# design.net
KiCad netlist of a schematic drawn in Altium Designer
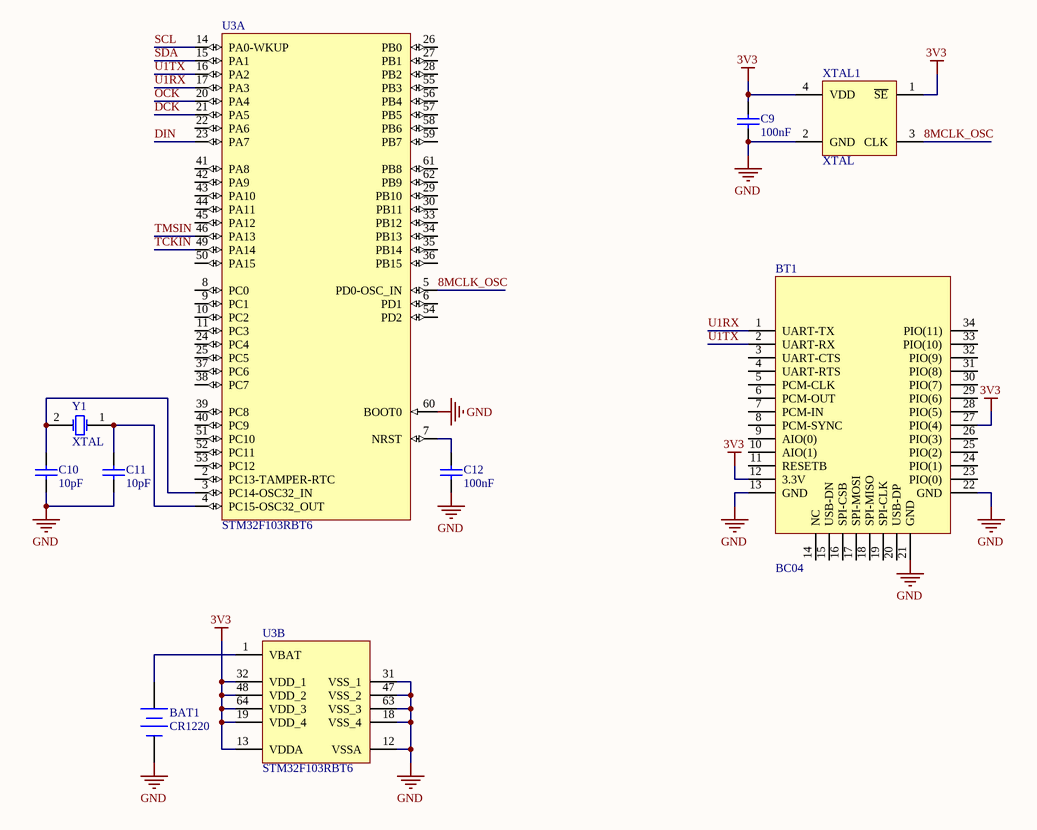
[diagram p0: 单片机.SchDoc]

(export (version "E")
  (design (tool "Eeschema 10.0.6"))
  (components
    (comp (ref "BAT1")
      (value "CR1220")
      (footprint "BAT-CR1220")
      (description "Multicell Battery")
      (fields (field (name "PUBLISHER") "Altium Limited"))
      (libsource (lib "yitiandelan") (part "Battery"))
    )
    (comp (ref "BT1") (value "BC04") (footprint "BC04") (libsource (lib "yitiandelan") (part "BC04")))
    (comp (ref "C9")
      (value "100nF")
      (footprint "0805")
      (description "Capacitor")
      (fields (field (name "PUBLISHER") "Altium Limited"))
      (libsource (lib "yitiandelan") (part "Cap"))
    )
    (comp (ref "C10")
      (value "10pF")
      (footprint "0805")
      (description "Capacitor")
      (fields (field (name "PUBLISHER") "Altium Limited"))
      (libsource (lib "yitiandelan") (part "Cap"))
    )
    (comp (ref "C11")
      (value "10pF")
      (footprint "0805")
      (description "Capacitor")
      (fields (field (name "PUBLISHER") "Altium Limited"))
      (libsource (lib "yitiandelan") (part "Cap"))
    )
    (comp (ref "C12")
      (value "100nF")
      (footprint "0805")
      (description "Capacitor")
      (fields (field (name "PUBLISHER") "Altium Limited"))
      (libsource (lib "yitiandelan") (part "Cap"))
    )
    (comp (ref "U3")
      (value "STM32F103RBT6")
      (footprint "LQFP-64")
      (libsource (lib "yitiandelan") (part "STM32F103RBT6"))
    )
    (comp (ref "XTAL1")
      (value "XTAL")
      (footprint "XTAL7050")
      (libsource (lib "yitiandelan") (part "XTAL_SMD"))
    )
    (comp (ref "Y1")
      (value "XTAL")
      (footprint "XTAL-32768")
      (description "Crystal Oscillator")
      (fields (field (name "PUBLISHER") "Altium Limited"))
      (libsource (lib "yitiandelan") (part "XTAL"))
    )
  )
  (nets
    (net (code "1") (name "/8MCLK_OSC") (class "Default")
      (node (ref "U3") (pin "5") (pinfunction "PD0-OSC_IN_5") (pintype "bidirectional"))
      (node (ref "XTAL1") (pin "3") (pinfunction "CLK_3") (pintype "passive"))
    )
    (net (code "2") (name "/DCK") (class "Default")
      (node (ref "U3") (pin "21") (pinfunction "PA5_21") (pintype "bidirectional"))
    )
    (net (code "3") (name "/DIN") (class "Default")
      (node (ref "U3") (pin "23") (pinfunction "PA7_23") (pintype "bidirectional"))
    )
    (net (code "4") (name "/OCK") (class "Default")
      (node (ref "U3") (pin "20") (pinfunction "PA4_20") (pintype "bidirectional"))
    )
    (net (code "5") (name "/SCL") (class "Default")
      (node (ref "U3") (pin "14") (pinfunction "PA0-WKUP_14") (pintype "bidirectional"))
    )
    (net (code "6") (name "/SDA") (class "Default")
      (node (ref "U3") (pin "15") (pinfunction "PA1_15") (pintype "bidirectional"))
    )
    (net (code "7") (name "/TCKIN") (class "Default")
      (node (ref "U3") (pin "49") (pinfunction "PA14_49") (pintype "bidirectional"))
    )
    (net (code "8") (name "/TMSIN") (class "Default")
      (node (ref "U3") (pin "46") (pinfunction "PA13_46") (pintype "bidirectional"))
    )
    (net (code "9") (name "/U1RX") (class "Default")
      (node (ref "BT1") (pin "1") (pinfunction "UART-TX_1") (pintype "passive"))
      (node (ref "U3") (pin "17") (pinfunction "PA3_17") (pintype "bidirectional"))
    )
    (net (code "10") (name "/U1TX") (class "Default")
      (node (ref "BT1") (pin "2") (pinfunction "UART-RX_2") (pintype "passive"))
      (node (ref "U3") (pin "16") (pinfunction "PA2_16") (pintype "bidirectional"))
    )
    (net (code "11") (name "3V3") (class "Default")
      (node (ref "BT1") (pin "12") (pinfunction "3.3V_12") (pintype "passive"))
      (node (ref "BT1") (pin "27") (pinfunction "PIO(4)_27") (pintype "passive"))
      (node (ref "C9") (pin "2") (pinfunction "2_2") (pintype "passive"))
      (node (ref "U3") (pin "13") (pinfunction "VDDA_13") (pintype "power_in"))
      (node (ref "U3") (pin "19") (pinfunction "VDD_4_19") (pintype "power_in"))
      (node (ref "U3") (pin "32") (pinfunction "VDD_1_32") (pintype "power_in"))
      (node (ref "U3") (pin "48") (pinfunction "VDD_2_48") (pintype "power_in"))
      (node (ref "U3") (pin "64") (pinfunction "VDD_3_64") (pintype "power_in"))
      (node (ref "XTAL1") (pin "1") (pinfunction "~{SE}_1") (pintype "passive"))
      (node (ref "XTAL1") (pin "4") (pinfunction "VDD_4") (pintype "passive"))
    )
    (net (code "12") (name "GND") (class "Default")
      (node (ref "BAT1") (pin "2") (pinfunction "-_2") (pintype "passive"))
      (node (ref "BT1") (pin "13") (pinfunction "GND_13") (pintype "passive"))
      (node (ref "BT1") (pin "21") (pinfunction "GND_21") (pintype "passive"))
      (node (ref "BT1") (pin "22") (pinfunction "GND_22") (pintype "passive"))
      (node (ref "C10") (pin "1") (pinfunction "1_1") (pintype "passive"))
      (node (ref "C11") (pin "1") (pinfunction "1_1") (pintype "passive"))
      (node (ref "C12") (pin "2") (pinfunction "2_2") (pintype "passive"))
      (node (ref "C9") (pin "1") (pinfunction "1_1") (pintype "passive"))
      (node (ref "U3") (pin "12") (pinfunction "VSSA_12") (pintype "power_in"))
      (node (ref "U3") (pin "18") (pinfunction "VSS_4_18") (pintype "power_in"))
      (node (ref "U3") (pin "31") (pinfunction "VSS_1_31") (pintype "power_in"))
      (node (ref "U3") (pin "47") (pinfunction "VSS_2_47") (pintype "power_in"))
      (node (ref "U3") (pin "60") (pinfunction "BOOT0_60") (pintype "input"))
      (node (ref "U3") (pin "63") (pinfunction "VSS_3_63") (pintype "power_in"))
      (node (ref "XTAL1") (pin "2") (pinfunction "GND_2") (pintype "passive"))
    )
    (net (code "13") (name "Net-(BAT1-+)") (class "Default")
      (node (ref "BAT1") (pin "1") (pinfunction "+_1") (pintype "passive"))
      (node (ref "U3") (pin "1") (pinfunction "VBAT_1") (pintype "power_in"))
    )
    (net (code "14") (name "Net-(U3A-NRST)") (class "Default")
      (node (ref "C12") (pin "1") (pinfunction "1_1") (pintype "passive"))
      (node (ref "U3") (pin "7") (pinfunction "NRST_7") (pintype "bidirectional"))
    )
    (net (code "15") (name "Net-(U3A-PC14-OSC32_IN)") (class "Default")
      (node (ref "C10") (pin "2") (pinfunction "2_2") (pintype "passive"))
      (node (ref "U3") (pin "3") (pinfunction "PC14-OSC32_IN_3") (pintype "bidirectional"))
      (node (ref "Y1") (pin "2") (pinfunction "OSC2_2") (pintype "passive"))
    )
    (net (code "16") (name "Net-(U3A-PC15-OSC32_OUT)") (class "Default")
      (node (ref "C11") (pin "2") (pinfunction "2_2") (pintype "passive"))
      (node (ref "U3") (pin "4") (pinfunction "PC15-OSC32_OUT_4") (pintype "bidirectional"))
      (node (ref "Y1") (pin "1") (pinfunction "OSC1_1") (pintype "passive"))
    )
    (net (code "17") (name "unconnected-(BT1-AIO(0)-Pad9)") (class "Default")
      (node (ref "BT1") (pin "9") (pinfunction "AIO(0)_9") (pintype "passive"))
    )
    (net (code "18") (name "unconnected-(BT1-AIO(1)-Pad10)") (class "Default")
      (node (ref "BT1") (pin "10") (pinfunction "AIO(1)_10") (pintype "passive"))
    )
    (net (code "19") (name "unconnected-(BT1-NC-Pad14)") (class "Default")
      (node (ref "BT1") (pin "14") (pinfunction "NC_14") (pintype "passive"))
    )
    (net (code "20") (name "unconnected-(BT1-PCM-CLK-Pad5)") (class "Default")
      (node (ref "BT1") (pin "5") (pinfunction "PCM-CLK_5") (pintype "passive"))
    )
    (net (code "21") (name "unconnected-(BT1-PCM-IN-Pad7)") (class "Default")
      (node (ref "BT1") (pin "7") (pinfunction "PCM-IN_7") (pintype "passive"))
    )
    (net (code "22") (name "unconnected-(BT1-PCM-OUT-Pad6)") (class "Default")
      (node (ref "BT1") (pin "6") (pinfunction "PCM-OUT_6") (pintype "passive"))
    )
    (net (code "23") (name "unconnected-(BT1-PCM-SYNC-Pad8)") (class "Default")
      (node (ref "BT1") (pin "8") (pinfunction "PCM-SYNC_8") (pintype "passive"))
    )
    (net (code "24") (name "unconnected-(BT1-PIO(0)-Pad23)") (class "Default")
      (node (ref "BT1") (pin "23") (pinfunction "PIO(0)_23") (pintype "passive"))
    )
    (net (code "25") (name "unconnected-(BT1-PIO(1)-Pad24)") (class "Default")
      (node (ref "BT1") (pin "24") (pinfunction "PIO(1)_24") (pintype "passive"))
    )
    (net (code "26") (name "unconnected-(BT1-PIO(2)-Pad25)") (class "Default")
      (node (ref "BT1") (pin "25") (pinfunction "PIO(2)_25") (pintype "passive"))
    )
    (net (code "27") (name "unconnected-(BT1-PIO(3)-Pad26)") (class "Default")
      (node (ref "BT1") (pin "26") (pinfunction "PIO(3)_26") (pintype "passive"))
    )
    (net (code "28") (name "unconnected-(BT1-PIO(5)-Pad28)") (class "Default")
      (node (ref "BT1") (pin "28") (pinfunction "PIO(5)_28") (pintype "passive"))
    )
    (net (code "29") (name "unconnected-(BT1-PIO(6)-Pad29)") (class "Default")
      (node (ref "BT1") (pin "29") (pinfunction "PIO(6)_29") (pintype "passive"))
    )
    (net (code "30") (name "unconnected-(BT1-PIO(7)-Pad30)") (class "Default")
      (node (ref "BT1") (pin "30") (pinfunction "PIO(7)_30") (pintype "passive"))
    )
    (net (code "31") (name "unconnected-(BT1-PIO(8)-Pad31)") (class "Default")
      (node (ref "BT1") (pin "31") (pinfunction "PIO(8)_31") (pintype "passive"))
    )
    (net (code "32") (name "unconnected-(BT1-PIO(9)-Pad32)") (class "Default")
      (node (ref "BT1") (pin "32") (pinfunction "PIO(9)_32") (pintype "passive"))
    )
    (net (code "33") (name "unconnected-(BT1-PIO(10)-Pad33)") (class "Default")
      (node (ref "BT1") (pin "33") (pinfunction "PIO(10)_33") (pintype "passive"))
    )
    (net (code "34") (name "unconnected-(BT1-PIO(11)-Pad34)") (class "Default")
      (node (ref "BT1") (pin "34") (pinfunction "PIO(11)_34") (pintype "passive"))
    )
    (net (code "35") (name "unconnected-(BT1-RESETB-Pad11)") (class "Default")
      (node (ref "BT1") (pin "11") (pinfunction "RESETB_11") (pintype "passive"))
    )
    (net (code "36") (name "unconnected-(BT1-SPI-CLK-Pad19)") (class "Default")
      (node (ref "BT1") (pin "19") (pinfunction "SPI-CLK_19") (pintype "passive"))
    )
    (net (code "37") (name "unconnected-(BT1-SPI-CSB-Pad16)") (class "Default")
      (node (ref "BT1") (pin "16") (pinfunction "SPI-CSB_16") (pintype "passive"))
    )
    (net (code "38") (name "unconnected-(BT1-SPI-MISO-Pad18)") (class "Default")
      (node (ref "BT1") (pin "18") (pinfunction "SPI-MISO_18") (pintype "passive"))
    )
    (net (code "39") (name "unconnected-(BT1-SPI-MOSI-Pad17)") (class "Default")
      (node (ref "BT1") (pin "17") (pinfunction "SPI-MOSI_17") (pintype "passive"))
    )
    (net (code "40") (name "unconnected-(BT1-UART-CTS-Pad3)") (class "Default")
      (node (ref "BT1") (pin "3") (pinfunction "UART-CTS_3") (pintype "passive"))
    )
    (net (code "41") (name "unconnected-(BT1-UART-RTS-Pad4)") (class "Default")
      (node (ref "BT1") (pin "4") (pinfunction "UART-RTS_4") (pintype "passive"))
    )
    (net (code "42") (name "unconnected-(BT1-USB-DN-Pad15)") (class "Default")
      (node (ref "BT1") (pin "15") (pinfunction "USB-DN_15") (pintype "passive"))
    )
    (net (code "43") (name "unconnected-(BT1-USB-DP-Pad20)") (class "Default")
      (node (ref "BT1") (pin "20") (pinfunction "USB-DP_20") (pintype "passive"))
    )
    (net (code "44") (name "unconnected-(U3A-PA6-Pad22)") (class "Default")
      (node (ref "U3") (pin "22") (pinfunction "PA6_22") (pintype "bidirectional"))
    )
    (net (code "45") (name "unconnected-(U3A-PA8-Pad41)") (class "Default")
      (node (ref "U3") (pin "41") (pinfunction "PA8_41") (pintype "bidirectional"))
    )
    (net (code "46") (name "unconnected-(U3A-PA9-Pad42)") (class "Default")
      (node (ref "U3") (pin "42") (pinfunction "PA9_42") (pintype "bidirectional"))
    )
    (net (code "47") (name "unconnected-(U3A-PA10-Pad43)") (class "Default")
      (node (ref "U3") (pin "43") (pinfunction "PA10_43") (pintype "bidirectional"))
    )
    (net (code "48") (name "unconnected-(U3A-PA11-Pad44)") (class "Default")
      (node (ref "U3") (pin "44") (pinfunction "PA11_44") (pintype "bidirectional"))
    )
    (net (code "49") (name "unconnected-(U3A-PA12-Pad45)") (class "Default")
      (node (ref "U3") (pin "45") (pinfunction "PA12_45") (pintype "bidirectional"))
    )
    (net (code "50") (name "unconnected-(U3A-PA15-Pad50)") (class "Default")
      (node (ref "U3") (pin "50") (pinfunction "PA15_50") (pintype "bidirectional"))
    )
    (net (code "51") (name "unconnected-(U3A-PB0-Pad26)") (class "Default")
      (node (ref "U3") (pin "26") (pinfunction "PB0_26") (pintype "bidirectional"))
    )
    (net (code "52") (name "unconnected-(U3A-PB1-Pad27)") (class "Default")
      (node (ref "U3") (pin "27") (pinfunction "PB1_27") (pintype "bidirectional"))
    )
    (net (code "53") (name "unconnected-(U3A-PB2-Pad28)") (class "Default")
      (node (ref "U3") (pin "28") (pinfunction "PB2_28") (pintype "bidirectional"))
    )
    (net (code "54") (name "unconnected-(U3A-PB3-Pad55)") (class "Default")
      (node (ref "U3") (pin "55") (pinfunction "PB3_55") (pintype "bidirectional"))
    )
    (net (code "55") (name "unconnected-(U3A-PB4-Pad56)") (class "Default")
      (node (ref "U3") (pin "56") (pinfunction "PB4_56") (pintype "bidirectional"))
    )
    (net (code "56") (name "unconnected-(U3A-PB5-Pad57)") (class "Default")
      (node (ref "U3") (pin "57") (pinfunction "PB5_57") (pintype "bidirectional"))
    )
    (net (code "57") (name "unconnected-(U3A-PB6-Pad58)") (class "Default")
      (node (ref "U3") (pin "58") (pinfunction "PB6_58") (pintype "bidirectional"))
    )
    (net (code "58") (name "unconnected-(U3A-PB7-Pad59)") (class "Default")
      (node (ref "U3") (pin "59") (pinfunction "PB7_59") (pintype "bidirectional"))
    )
    (net (code "59") (name "unconnected-(U3A-PB8-Pad61)") (class "Default")
      (node (ref "U3") (pin "61") (pinfunction "PB8_61") (pintype "bidirectional"))
    )
    (net (code "60") (name "unconnected-(U3A-PB9-Pad62)") (class "Default")
      (node (ref "U3") (pin "62") (pinfunction "PB9_62") (pintype "bidirectional"))
    )
    (net (code "61") (name "unconnected-(U3A-PB10-Pad29)") (class "Default")
      (node (ref "U3") (pin "29") (pinfunction "PB10_29") (pintype "bidirectional"))
    )
    (net (code "62") (name "unconnected-(U3A-PB11-Pad30)") (class "Default")
      (node (ref "U3") (pin "30") (pinfunction "PB11_30") (pintype "bidirectional"))
    )
    (net (code "63") (name "unconnected-(U3A-PB12-Pad33)") (class "Default")
      (node (ref "U3") (pin "33") (pinfunction "PB12_33") (pintype "bidirectional"))
    )
    (net (code "64") (name "unconnected-(U3A-PB13-Pad34)") (class "Default")
      (node (ref "U3") (pin "34") (pinfunction "PB13_34") (pintype "bidirectional"))
    )
    (net (code "65") (name "unconnected-(U3A-PB14-Pad35)") (class "Default")
      (node (ref "U3") (pin "35") (pinfunction "PB14_35") (pintype "bidirectional"))
    )
    (net (code "66") (name "unconnected-(U3A-PB15-Pad36)") (class "Default")
      (node (ref "U3") (pin "36") (pinfunction "PB15_36") (pintype "bidirectional"))
    )
    (net (code "67") (name "unconnected-(U3A-PC0-Pad8)") (class "Default")
      (node (ref "U3") (pin "8") (pinfunction "PC0_8") (pintype "bidirectional"))
    )
    (net (code "68") (name "unconnected-(U3A-PC1-Pad9)") (class "Default")
      (node (ref "U3") (pin "9") (pinfunction "PC1_9") (pintype "bidirectional"))
    )
    (net (code "69") (name "unconnected-(U3A-PC2-Pad10)") (class "Default")
      (node (ref "U3") (pin "10") (pinfunction "PC2_10") (pintype "bidirectional"))
    )
    (net (code "70") (name "unconnected-(U3A-PC3-Pad11)") (class "Default")
      (node (ref "U3") (pin "11") (pinfunction "PC3_11") (pintype "bidirectional"))
    )
    (net (code "71") (name "unconnected-(U3A-PC4-Pad24)") (class "Default")
      (node (ref "U3") (pin "24") (pinfunction "PC4_24") (pintype "bidirectional"))
    )
    (net (code "72") (name "unconnected-(U3A-PC5-Pad25)") (class "Default")
      (node (ref "U3") (pin "25") (pinfunction "PC5_25") (pintype "bidirectional"))
    )
    (net (code "73") (name "unconnected-(U3A-PC6-Pad37)") (class "Default")
      (node (ref "U3") (pin "37") (pinfunction "PC6_37") (pintype "bidirectional"))
    )
    (net (code "74") (name "unconnected-(U3A-PC7-Pad38)") (class "Default")
      (node (ref "U3") (pin "38") (pinfunction "PC7_38") (pintype "bidirectional"))
    )
    (net (code "75") (name "unconnected-(U3A-PC8-Pad39)") (class "Default")
      (node (ref "U3") (pin "39") (pinfunction "PC8_39") (pintype "bidirectional"))
    )
    (net (code "76") (name "unconnected-(U3A-PC9-Pad40)") (class "Default")
      (node (ref "U3") (pin "40") (pinfunction "PC9_40") (pintype "bidirectional"))
    )
    (net (code "77") (name "unconnected-(U3A-PC10-Pad51)") (class "Default")
      (node (ref "U3") (pin "51") (pinfunction "PC10_51") (pintype "bidirectional"))
    )
    (net (code "78") (name "unconnected-(U3A-PC11-Pad52)") (class "Default")
      (node (ref "U3") (pin "52") (pinfunction "PC11_52") (pintype "bidirectional"))
    )
    (net (code "79") (name "unconnected-(U3A-PC12-Pad53)") (class "Default")
      (node (ref "U3") (pin "53") (pinfunction "PC12_53") (pintype "bidirectional"))
    )
    (net (code "80") (name "unconnected-(U3A-PC13-TAMPER-RTC-Pad2)") (class "Default")
      (node (ref "U3") (pin "2") (pinfunction "PC13-TAMPER-RTC_2") (pintype "bidirectional"))
    )
    (net (code "81") (name "unconnected-(U3A-PD1-Pad6)") (class "Default")
      (node (ref "U3") (pin "6") (pinfunction "PD1_6") (pintype "bidirectional"))
    )
    (net (code "82") (name "unconnected-(U3A-PD2-Pad54)") (class "Default")
      (node (ref "U3") (pin "54") (pinfunction "PD2_54") (pintype "bidirectional"))
    )
  )
)
